# ShineSensor.net
KiCad netlist of a schematic drawn in EAGLE
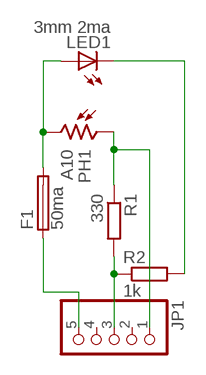
[diagram p0: schematic, sheet 1]

(export (version "E")
  (design (tool "Eeschema 10.0.6"))
  (components
    (comp (ref "F1")
      (value "50ma")
      (footprint "eagle-import:MF-SMDF050")
      (libsource (lib "eagle-import") (part "MF-SMDF050"))
    )
    (comp (ref "JP1")
      (value "PINHD-1X5/90")
      (footprint "eagle-import:1X05_90")
      (libsource (lib "eagle-import") (part "PINHD-1X5/90"))
    )
    (comp (ref "LED1")
      (value "3mm 2ma")
      (footprint "eagle-import:LED3MM")
      (fields (field (name "MF") "VISHAY SEMICONDUCTOR"))
      (libsource (lib "eagle-import") (part "TLLY4400"))
    )
    (comp (ref "PH1")
      (value "A10")
      (footprint "eagle-import:T0-46-A10XX")
      (libsource (lib "eagle-import") (part "A1050_11"))
    )
    (comp (ref "R1")
      (value "330")
      (footprint "eagle-import:R1206")
      (libsource (lib "eagle-import") (part "R-EU_R1206"))
    )
    (comp (ref "R2")
      (value "1k")
      (footprint "eagle-import:R1206")
      (libsource (lib "eagle-import") (part "R-EU_R1206"))
    )
  )
  (nets
    (net (code "1") (name "Net-(F1-Pad1)") (class "Default")
      (node (ref "F1") (pin "1") (pinfunction "1_1") (pintype "passive"))
      (node (ref "JP1") (pin "5") (pinfunction "5_5") (pintype "passive"))
    )
    (net (code "2") (name "Net-(F1-Pad2)") (class "Default")
      (node (ref "F1") (pin "2") (pinfunction "2_2") (pintype "passive"))
      (node (ref "LED1") (pin "A") (pinfunction "A_A") (pintype "passive"))
      (node (ref "PH1") (pin "2") (pinfunction "2_2") (pintype "passive"))
    )
    (net (code "3") (name "Net-(JP1-Pad1)") (class "Default")
      (node (ref "JP1") (pin "1") (pinfunction "1_1") (pintype "passive"))
      (node (ref "PH1") (pin "1") (pinfunction "1_1") (pintype "passive"))
      (node (ref "R1") (pin "1") (pinfunction "1_1") (pintype "passive"))
    )
    (net (code "4") (name "Net-(JP1-Pad3)") (class "Default")
      (node (ref "JP1") (pin "3") (pinfunction "3_3") (pintype "passive"))
      (node (ref "R1") (pin "2") (pinfunction "2_2") (pintype "passive"))
      (node (ref "R2") (pin "1") (pinfunction "1_1") (pintype "passive"))
    )
    (net (code "5") (name "Net-(LED1-C)") (class "Default")
      (node (ref "LED1") (pin "K") (pinfunction "C_K") (pintype "passive"))
      (node (ref "R2") (pin "2") (pinfunction "2_2") (pintype "passive"))
    )
    (net (code "6") (name "unconnected-(JP1-Pad2)") (class "Default")
      (node (ref "JP1") (pin "2") (pinfunction "2_2") (pintype "passive"))
    )
    (net (code "7") (name "unconnected-(JP1-Pad4)") (class "Default")
      (node (ref "JP1") (pin "4") (pinfunction "4_4") (pintype "passive"))
    )
  )
)
